# CtrlCarbinBoard_Common.net
KiCad netlist of a schematic drawn in Altium Designer
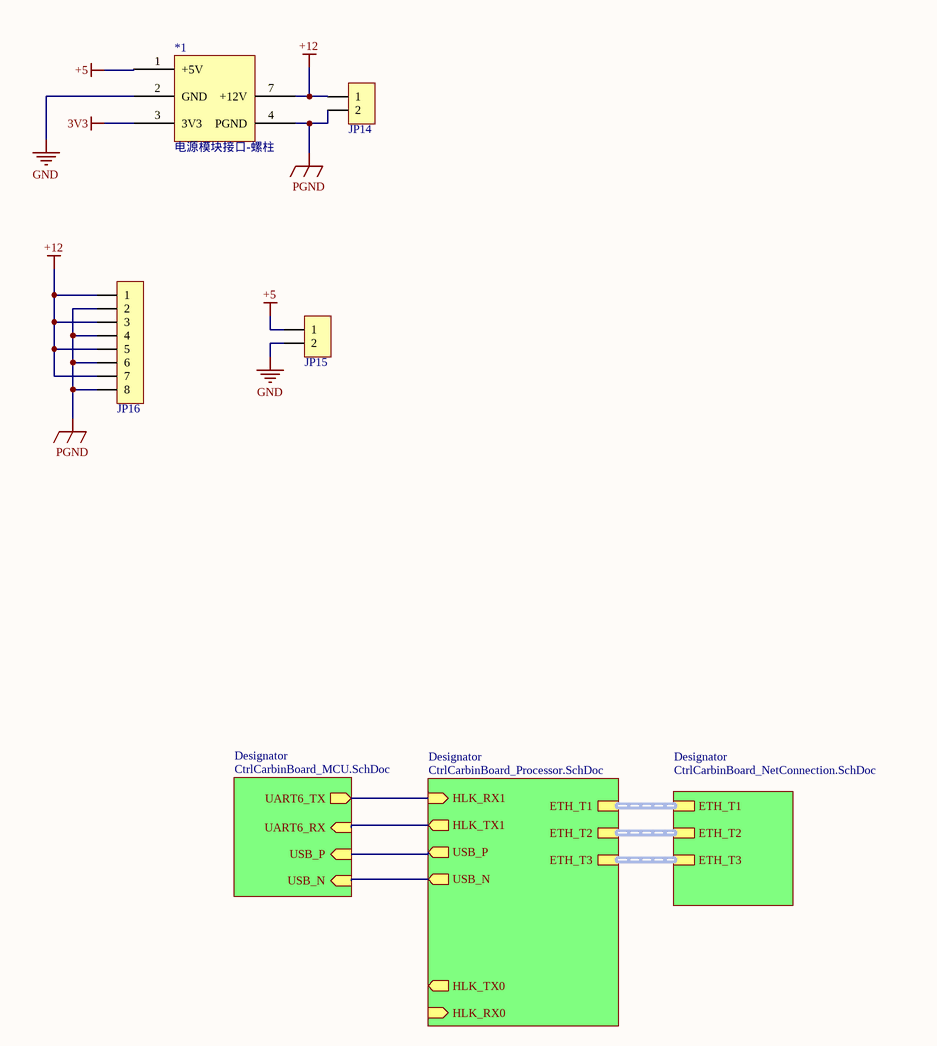
[diagram p0: CtrlCarbinBoard_Common.SchDoc]

(export (version "E")
  (design (tool "Eeschema 10.0.6"))
  (components
    (comp (ref "*1") (value "电源模块接口-螺柱") (footprint "螺柱-座 5") (libsource (lib "MySchLib") (part "电源模块接口-螺柱")))
    (comp (ref "JP14")
      (value "HDR-1X2")
      (footprint "KF128-5.08-2P")
      (description "2P接插件")
      (fields (field (name "版权归属") "源创客"))
      (libsource (lib "4.10 - 接插件-脚距5.08") (part "Header 2"))
    )
    (comp (ref "JP15")
      (value "HDR-1X2")
      (footprint "KF128-5.08-2P")
      (description "2P接插件")
      (fields (field (name "版权归属") "源创客"))
      (libsource (lib "4.10 - 接插件-脚距5.08") (part "Header 2"))
    )
    (comp (ref "JP16")
      (value "HDR-1X8")
      (footprint "KF128-5.08-8P")
      (description "8P接插件")
      (fields (field (name "版权归属") "源创客"))
      (libsource (lib "4.10 - 接插件-脚距5.08") (part "Header 8"))
    )
  )
  (nets
    (net (code "1") (name "+5") (class "Default")
      (node (ref "*1") (pin "1") (pinfunction "+5V_1") (pintype "passive"))
      (node (ref "JP15") (pin "1") (pinfunction "1_1") (pintype "passive"))
    )
    (net (code "2") (name "+12") (class "Default")
      (node (ref "*1") (pin "7") (pinfunction "+12V_7") (pintype "passive"))
      (node (ref "JP14") (pin "1") (pinfunction "1_1") (pintype "passive"))
      (node (ref "JP16") (pin "1") (pinfunction "1_1") (pintype "passive"))
      (node (ref "JP16") (pin "3") (pinfunction "3_3") (pintype "passive"))
      (node (ref "JP16") (pin "5") (pinfunction "5_5") (pintype "passive"))
      (node (ref "JP16") (pin "7") (pinfunction "7_7") (pintype "passive"))
    )
    (net (code "12") (name "3V3") (class "Default")
      (node (ref "*1") (pin "3") (pinfunction "3V3_3") (pintype "passive"))
    )
    (net (code "13") (name "GND") (class "Default")
      (node (ref "*1") (pin "2") (pinfunction "GND_2") (pintype "passive"))
      (node (ref "JP15") (pin "2") (pinfunction "2_2") (pintype "passive"))
    )
    (net (code "14") (name "PGND") (class "Default")
      (node (ref "*1") (pin "4") (pinfunction "PGND_4") (pintype "passive"))
      (node (ref "JP14") (pin "2") (pinfunction "2_2") (pintype "passive"))
      (node (ref "JP16") (pin "2") (pinfunction "2_2") (pintype "passive"))
      (node (ref "JP16") (pin "4") (pinfunction "4_4") (pintype "passive"))
      (node (ref "JP16") (pin "6") (pinfunction "6_6") (pintype "passive"))
      (node (ref "JP16") (pin "8") (pinfunction "8_8") (pintype "passive"))
    )
  )
)
